# SwitchPower.net
KiCad netlist of a schematic drawn in Altium Designer
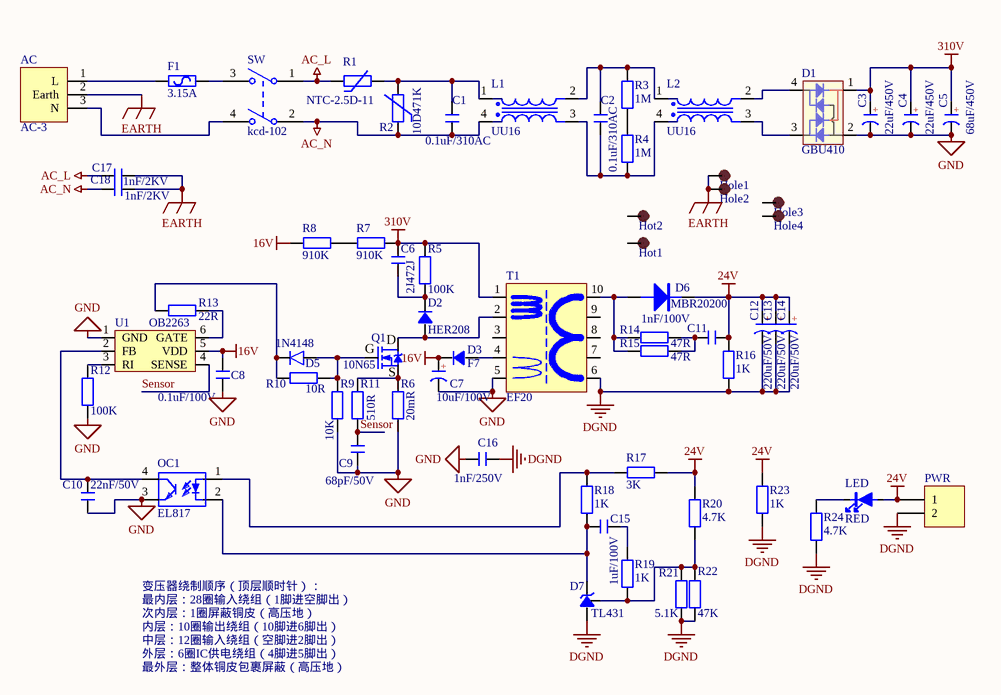
[diagram p0: SwitchPower.SchDoc]

(export (version "E")
  (design (tool "Eeschema 10.0.6"))
  (components
    (comp (ref "AC")
      (value "AC-3")
      (footprint "AC-3_1")
      (description "交流市电接口3芯")
      (libsource (lib "LovelessingSch") (part "AC-3"))
    )
    (comp (ref "C1")
      (value "0.1uF/310AC")
      (footprint "CX 10*13*11")
      (description "无极性贴片电容")
      (libsource (lib "LovelessingSch") (part "C"))
    )
    (comp (ref "C2")
      (value "0.1uF/310AC")
      (footprint "CX 10*13*11")
      (description "无极性贴片电容")
      (libsource (lib "LovelessingSch") (part "C"))
    )
    (comp (ref "C3")
      (value "22uF/450V")
      (footprint "CAP 5.0*12.5*20 - GD")
      (description "贴片电解电容")
      (libsource (lib "LovelessingSch") (part "C-CM"))
    )
    (comp (ref "C4")
      (value "22uF/450V")
      (footprint "CAP 5.0*12.5*20 - GD")
      (description "贴片电解电容")
      (libsource (lib "LovelessingSch") (part "C-CM"))
    )
    (comp (ref "C5")
      (value "68uF/450V")
      (footprint "CAP 7.5*18*35.5-H - GD")
      (description "贴片电解电容")
      (libsource (lib "LovelessingSch") (part "C-CM"))
    )
    (comp (ref "C6")
      (value "2J472J")
      (footprint "CBB 5*6.3*3")
      (description "无极性贴片电容")
      (libsource (lib "LovelessingSch") (part "C"))
    )
    (comp (ref "C7")
      (value "10uF/100V")
      (footprint "CAP 2.5*5*11 - GD")
      (description "贴片电解电容")
      (libsource (lib "LovelessingSch") (part "C-CM"))
    )
    (comp (ref "C8")
      (value "0.1uF/100V")
      (footprint "C 0805_L")
      (description "无极性贴片电容")
      (libsource (lib "LovelessingSch") (part "C"))
    )
    (comp (ref "C9")
      (value "68pF/50V")
      (footprint "C 0805_L")
      (description "无极性贴片电容")
      (libsource (lib "LovelessingSch") (part "C"))
    )
    (comp (ref "C10")
      (value "22nF/50V")
      (footprint "C 0805_L")
      (description "无极性贴片电容")
      (libsource (lib "LovelessingSch") (part "C"))
    )
    (comp (ref "C11")
      (value "1nF/100V")
      (footprint "C 1206_L")
      (description "无极性贴片电容")
      (libsource (lib "LovelessingSch") (part "C"))
    )
    (comp (ref "C12")
      (value "220uF/50V")
      (footprint "CAP 5.0*10*20 - GD")
      (description "贴片电解电容")
      (libsource (lib "LovelessingSch") (part "C-CM"))
    )
    (comp (ref "C13")
      (value "220uF/50V")
      (footprint "CAP 5.0*10*20 - GD")
      (description "贴片电解电容")
      (libsource (lib "LovelessingSch") (part "C-CM"))
    )
    (comp (ref "C14")
      (value "220uF/50V")
      (footprint "CAP 5.0*10*20 - GD")
      (description "贴片电解电容")
      (libsource (lib "LovelessingSch") (part "C-CM"))
    )
    (comp (ref "C15")
      (value "1uF/100V")
      (footprint "C 1206_L")
      (description "无极性贴片电容")
      (libsource (lib "LovelessingSch") (part "C"))
    )
    (comp (ref "C16")
      (value "1nF/250V")
      (footprint "CY 10*14*5")
      (description "无极性贴片电容")
      (libsource (lib "LovelessingSch") (part "C"))
    )
    (comp (ref "C17")
      (value "1nF/2KV")
      (footprint "CY 10*14*5")
      (description "无极性贴片电容")
      (libsource (lib "LovelessingSch") (part "C"))
    )
    (comp (ref "C18")
      (value "1nF/2KV")
      (footprint "CY 10*14*5")
      (description "无极性贴片电容")
      (libsource (lib "LovelessingSch") (part "C"))
    )
    (comp (ref "D1")
      (value "GBU410")
      (footprint "GBU")
      (description "整流桥")
      (libsource (lib "LovelessingSch") (part "RectifierBridge"))
    )
    (comp (ref "D2")
      (value "HER208")
      (footprint "DO-15V")
      (description "开关二级管")
      (libsource (lib "LovelessingSch") (part "D-US1M"))
    )
    (comp (ref "D3")
      (value "F7")
      (footprint "SOD-123F")
      (description "开关二级管")
      (libsource (lib "LovelessingSch") (part "D-US1M"))
    )
    (comp (ref "D5")
      (value "1N4148")
      (footprint "SOD-123F")
      (description "二极管")
      (libsource (lib "LovelessingSch") (part "D"))
    )
    (comp (ref "D6")
      (value "MBR20200")
      (footprint "TO220A")
      (description "整流二极管")
      (libsource (lib "LovelessingSch") (part "DIODE"))
    )
    (comp (ref "D7")
      (value "TL431")
      (footprint "SOT23-3L")
      (description "稳压二极管")
      (libsource (lib "LovelessingSch") (part "TL431"))
    )
    (comp (ref "F1")
      (value "3.15A")
      (footprint "FU 4x16_V")
      (description "保险丝")
      (libsource (lib "LovelessingSch") (part "FUSE"))
    )
    (comp (ref "Hole1")
      (value "hole")
      (footprint "M3")
      (description "测试点")
      (libsource (lib "LovelessingSch") (part "TEST-POINT"))
    )
    (comp (ref "Hole2")
      (value "hole")
      (footprint "M3")
      (description "测试点")
      (libsource (lib "LovelessingSch") (part "TEST-POINT"))
    )
    (comp (ref "Hole3")
      (value "hole")
      (footprint "M3")
      (description "测试点")
      (libsource (lib "LovelessingSch") (part "TEST-POINT"))
    )
    (comp (ref "Hole4")
      (value "hole")
      (footprint "M3")
      (description "测试点")
      (libsource (lib "LovelessingSch") (part "TEST-POINT"))
    )
    (comp (ref "Hot1")
      (value "TEST POINT")
      (footprint "SRP16-24-25")
      (description "测试点")
      (libsource (lib "LovelessingSch") (part "TEST-POINT"))
    )
    (comp (ref "Hot2")
      (value "TEST POINT")
      (footprint "SRP16-24-25")
      (description "测试点")
      (libsource (lib "LovelessingSch") (part "TEST-POINT"))
    )
    (comp (ref "L1")
      (value "UU16")
      (footprint "UU10.5")
      (description "共模电感")
      (libsource (lib "LovelessingSch") (part "DLW21SN900SQ2L"))
    )
    (comp (ref "L2")
      (value "UU16")
      (footprint "UU10.5")
      (description "共模电感")
      (libsource (lib "LovelessingSch") (part "DLW21SN900SQ2L"))
    )
    (comp (ref "LED")
      (value "RED")
      (footprint "LED 0805R")
      (description "发光二极管")
      (libsource (lib "LovelessingSch") (part "LED"))
    )
    (comp (ref "OC1")
      (value "EL817")
      (footprint "DIP4-300")
      (description "线性光耦")
      (libsource (lib "LovelessingSch") (part "EL817"))
    )
    (comp (ref "PWR")
      (value "~")
      (footprint "VH3.96-LI-2P")
      (description "Header, 2-Pin")
      (fields (field (name "PUBLISHER") "Altium Limited"))
      (libsource (lib "LovelessingSch") (part "Header 2"))
    )
    (comp (ref "Q1")
      (value "10N65")
      (footprint "TO220A")
      (description "NMOS 75V+80A 7.4mΩ")
      (libsource (lib "LovelessingSch") (part "IRFS3607PBF"))
    )
    (comp (ref "R1")
      (value "NTC-2.5D-11")
      (footprint "VDR NTC2.5D-11")
      (description "热敏电阻")
      (libsource (lib "LovelessingSch") (part "R_NTC"))
    )
    (comp (ref "R2")
      (value "10D471K")
      (footprint "R VDR-12.5*16.5-T")
      (description "压敏电阻")
      (libsource (lib "LovelessingSch") (part "R_VDR"))
    )
    (comp (ref "R3")
      (value "1M")
      (footprint "R 1206_L")
      (description "贴片电阻")
      (libsource (lib "LovelessingSch") (part "R"))
    )
    (comp (ref "R4")
      (value "1M")
      (footprint "R 1206_L")
      (description "贴片电阻")
      (libsource (lib "LovelessingSch") (part "R"))
    )
    (comp (ref "R5")
      (value "100K")
      (footprint "AXIAL0.8-2W-V")
      (description "贴片电阻")
      (libsource (lib "LovelessingSch") (part "R"))
    )
    (comp (ref "R6")
      (value "20mR")
      (footprint "AXIAL0.8-2W-V")
      (description "贴片电阻")
      (libsource (lib "LovelessingSch") (part "R"))
    )
    (comp (ref "R7")
      (value "910K")
      (footprint "R 1206_L")
      (description "贴片电阻")
      (libsource (lib "LovelessingSch") (part "R"))
    )
    (comp (ref "R8")
      (value "910K")
      (footprint "R 1206_L")
      (description "贴片电阻")
      (libsource (lib "LovelessingSch") (part "R"))
    )
    (comp (ref "R9")
      (value "10K")
      (footprint "R 1206_L")
      (description "贴片电阻")
      (libsource (lib "LovelessingSch") (part "R"))
    )
    (comp (ref "R10")
      (value "10R")
      (footprint "R 0805_L")
      (description "贴片电阻")
      (libsource (lib "LovelessingSch") (part "R"))
    )
    (comp (ref "R11")
      (value "510R")
      (footprint "R 1206_L")
      (description "贴片电阻")
      (libsource (lib "LovelessingSch") (part "R"))
    )
    (comp (ref "R12")
      (value "100K")
      (footprint "R 0805_L")
      (description "贴片电阻")
      (libsource (lib "LovelessingSch") (part "R"))
    )
    (comp (ref "R13")
      (value "22R")
      (footprint "R 1206_L")
      (description "贴片电阻")
      (libsource (lib "LovelessingSch") (part "R"))
    )
    (comp (ref "R14")
      (value "47R")
      (footprint "R 1206_L")
      (description "贴片电阻")
      (libsource (lib "LovelessingSch") (part "R"))
    )
    (comp (ref "R15")
      (value "47R")
      (footprint "R 1206_L")
      (description "贴片电阻")
      (libsource (lib "LovelessingSch") (part "R"))
    )
    (comp (ref "R16")
      (value "1K")
      (footprint "R 1206_L")
      (description "贴片电阻")
      (libsource (lib "LovelessingSch") (part "R"))
    )
    (comp (ref "R17")
      (value "3K")
      (footprint "R 0805_L")
      (description "贴片电阻")
      (libsource (lib "LovelessingSch") (part "R"))
    )
    (comp (ref "R18")
      (value "1K")
      (footprint "R 0805_L")
      (description "贴片电阻")
      (libsource (lib "LovelessingSch") (part "R"))
    )
    (comp (ref "R19")
      (value "1K")
      (footprint "R 0805_L")
      (description "贴片电阻")
      (libsource (lib "LovelessingSch") (part "R"))
    )
    (comp (ref "R20")
      (value "4.7K")
      (footprint "R 0805_L")
      (description "贴片电阻")
      (libsource (lib "LovelessingSch") (part "R"))
    )
    (comp (ref "R21")
      (value "5.1K")
      (footprint "R 0805_L")
      (description "贴片电阻")
      (libsource (lib "LovelessingSch") (part "R"))
    )
    (comp (ref "R22")
      (value "47K")
      (footprint "R 0805_L")
      (description "贴片电阻")
      (libsource (lib "LovelessingSch") (part "R"))
    )
    (comp (ref "R23")
      (value "1K")
      (footprint "R 1206_L")
      (description "贴片电阻")
      (libsource (lib "LovelessingSch") (part "R"))
    )
    (comp (ref "R24")
      (value "4.7K")
      (footprint "R 1206_L")
      (description "贴片电阻")
      (libsource (lib "LovelessingSch") (part "R"))
    )
    (comp (ref "SW")
      (value "kcd-102")
      (footprint "KCD1-104-W")
      (description "双刀单掷开关")
      (libsource (lib "LovelessingSch") (part "Switch_2"))
    )
    (comp (ref "T1")
      (value "EF20")
      (footprint "EI28X30")
      (description "开关电源变压器")
      (libsource (lib "LovelessingSch") (part "EF20"))
    )
    (comp (ref "U1")
      (value "OB2263")
      (footprint "SOT23-6L")
      (description "开关电源IC")
      (libsource (lib "LovelessingSch") (part "OB2263"))
    )
  )
  (nets
    (net (code "1") (name "/Sensor") (class "Default")
      (node (ref "C9") (pin "1") (pinfunction "1_1") (pintype "passive"))
      (node (ref "R11") (pin "1") (pinfunction "1_1") (pintype "passive"))
      (node (ref "U1") (pin "4") (pinfunction "SENSE_4") (pintype "passive"))
    )
    (net (code "2") (name "16V") (class "Default")
      (node (ref "C7") (pin "1") (pinfunction "A_1") (pintype "passive"))
      (node (ref "C8") (pin "1") (pinfunction "1_1") (pintype "passive"))
      (node (ref "D3") (pin "2") (pinfunction "2_2") (pintype "passive"))
      (node (ref "R8") (pin "1") (pinfunction "1_1") (pintype "passive"))
      (node (ref "U1") (pin "5") (pinfunction "VDD_5") (pintype "passive"))
    )
    (net (code "3") (name "24V") (class "Default")
      (node (ref "C11") (pin "1") (pinfunction "1_1") (pintype "passive"))
      (node (ref "C12") (pin "1") (pinfunction "A_1") (pintype "passive"))
      (node (ref "C13") (pin "1") (pinfunction "A_1") (pintype "passive"))
      (node (ref "C14") (pin "1") (pinfunction "A_1") (pintype "passive"))
      (node (ref "D6") (pin "2") (pinfunction "K_2") (pintype "passive"))
      (node (ref "LED") (pin "1") (pinfunction "1_1") (pintype "passive"))
      (node (ref "PWR") (pin "1") (pinfunction "1_1") (pintype "passive"))
      (node (ref "R16") (pin "1") (pinfunction "1_1") (pintype "passive"))
      (node (ref "R17") (pin "1") (pinfunction "1_1") (pintype "passive"))
      (node (ref "R20") (pin "2") (pinfunction "2_2") (pintype "passive"))
      (node (ref "R23") (pin "1") (pinfunction "1_1") (pintype "passive"))
    )
    (net (code "4") (name "310V") (class "Default")
      (node (ref "C3") (pin "1") (pinfunction "A_1") (pintype "passive"))
      (node (ref "C4") (pin "1") (pinfunction "A_1") (pintype "passive"))
      (node (ref "C5") (pin "1") (pinfunction "A_1") (pintype "passive"))
      (node (ref "C6") (pin "2") (pinfunction "2_2") (pintype "passive"))
      (node (ref "D1") (pin "1") (pinfunction "+_1") (pintype "passive"))
      (node (ref "R5") (pin "2") (pinfunction "2_2") (pintype "passive"))
      (node (ref "R7") (pin "2") (pinfunction "2_2") (pintype "passive"))
      (node (ref "T1") (pin "1") (pinfunction "GND_1") (pintype "passive"))
    )
    (net (code "5") (name "AC_L") (class "Default")
      (node (ref "C17") (pin "2") (pinfunction "2_2") (pintype "passive"))
      (node (ref "R1") (pin "1") (pinfunction "1_1") (pintype "passive"))
      (node (ref "SW") (pin "1") (pinfunction "1_1") (pintype "passive"))
    )
    (net (code "6") (name "AC_N") (class "Default")
      (node (ref "C1") (pin "1") (pinfunction "1_1") (pintype "passive"))
      (node (ref "C18") (pin "2") (pinfunction "2_2") (pintype "passive"))
      (node (ref "L1") (pin "4") (pintype "passive"))
      (node (ref "R2") (pin "1") (pinfunction "1_1") (pintype "passive"))
      (node (ref "SW") (pin "2") (pinfunction "2_2") (pintype "passive"))
    )
    (net (code "7") (name "DGND") (class "Default")
      (node (ref "C12") (pin "2") (pinfunction "K_2") (pintype "passive"))
      (node (ref "C13") (pin "2") (pinfunction "K_2") (pintype "passive"))
      (node (ref "C14") (pin "2") (pinfunction "K_2") (pintype "passive"))
      (node (ref "C16") (pin "1") (pinfunction "1_1") (pintype "passive"))
      (node (ref "D7") (pin "3") (pintype "passive"))
      (node (ref "PWR") (pin "2") (pinfunction "2_2") (pintype "passive"))
      (node (ref "R16") (pin "2") (pinfunction "2_2") (pintype "passive"))
      (node (ref "R21") (pin "1") (pinfunction "1_1") (pintype "passive"))
      (node (ref "R22") (pin "1") (pinfunction "1_1") (pintype "passive"))
      (node (ref "R23") (pin "2") (pinfunction "2_2") (pintype "passive"))
      (node (ref "R24") (pin "2") (pinfunction "2_2") (pintype "passive"))
      (node (ref "T1") (pin "6") (pinfunction "DRAIN_6") (pintype "passive"))
    )
    (net (code "8") (name "EARTH") (class "Default")
      (node (ref "AC") (pin "2") (pinfunction "Earth_2") (pintype "passive"))
      (node (ref "C17") (pin "1") (pinfunction "1_1") (pintype "passive"))
      (node (ref "C18") (pin "1") (pinfunction "1_1") (pintype "passive"))
      (node (ref "Hole1") (pin "1") (pinfunction "1_1") (pintype "passive"))
      (node (ref "Hole2") (pin "1") (pinfunction "1_1") (pintype "passive"))
    )
    (net (code "9") (name "GND") (class "Default")
      (node (ref "C10") (pin "2") (pinfunction "2_2") (pintype "passive"))
      (node (ref "C16") (pin "2") (pinfunction "2_2") (pintype "passive"))
      (node (ref "C3") (pin "2") (pinfunction "K_2") (pintype "passive"))
      (node (ref "C4") (pin "2") (pinfunction "K_2") (pintype "passive"))
      (node (ref "C5") (pin "2") (pinfunction "K_2") (pintype "passive"))
      (node (ref "C7") (pin "2") (pinfunction "K_2") (pintype "passive"))
      (node (ref "C8") (pin "2") (pinfunction "2_2") (pintype "passive"))
      (node (ref "C9") (pin "2") (pinfunction "2_2") (pintype "passive"))
      (node (ref "D1") (pin "2") (pinfunction "-_2") (pintype "passive"))
      (node (ref "OC1") (pin "3") (pinfunction "E_3") (pintype "passive"))
      (node (ref "R12") (pin "1") (pinfunction "1_1") (pintype "passive"))
      (node (ref "R6") (pin "1") (pinfunction "1_1") (pintype "passive"))
      (node (ref "R9") (pin "1") (pinfunction "1_1") (pintype "passive"))
      (node (ref "T1") (pin "5") (pinfunction "DRAIN_5") (pintype "passive"))
      (node (ref "U1") (pin "1") (pinfunction "GND_1") (pintype "passive"))
    )
    (net (code "10") (name "Net-(AC-L)") (class "Default")
      (node (ref "AC") (pin "1") (pinfunction "L_1") (pintype "passive"))
      (node (ref "F1") (pin "1") (pinfunction "1_1") (pintype "passive"))
    )
    (net (code "11") (name "Net-(AC-N)") (class "Default")
      (node (ref "AC") (pin "3") (pinfunction "N_3") (pintype "passive"))
      (node (ref "SW") (pin "4") (pinfunction "4_4") (pintype "passive"))
    )
    (net (code "12") (name "Net-(C1-Pad2)") (class "Default")
      (node (ref "C1") (pin "2") (pinfunction "2_2") (pintype "passive"))
      (node (ref "L1") (pin "1") (pintype "passive"))
      (node (ref "R1") (pin "2") (pinfunction "2_2") (pintype "passive"))
      (node (ref "R2") (pin "2") (pinfunction "2_2") (pintype "passive"))
    )
    (net (code "13") (name "Net-(C2-Pad1)") (class "Default")
      (node (ref "C2") (pin "1") (pinfunction "1_1") (pintype "passive"))
      (node (ref "L1") (pin "3") (pintype "passive"))
      (node (ref "L2") (pin "4") (pintype "passive"))
      (node (ref "R4") (pin "1") (pinfunction "1_1") (pintype "passive"))
    )
    (net (code "14") (name "Net-(C2-Pad2)") (class "Default")
      (node (ref "C2") (pin "2") (pinfunction "2_2") (pintype "passive"))
      (node (ref "L1") (pin "2") (pintype "passive"))
      (node (ref "L2") (pin "1") (pintype "passive"))
      (node (ref "R3") (pin "2") (pinfunction "2_2") (pintype "passive"))
    )
    (net (code "15") (name "Net-(C6-Pad1)") (class "Default")
      (node (ref "C6") (pin "1") (pinfunction "1_1") (pintype "passive"))
      (node (ref "D2") (pin "2") (pinfunction "2_2") (pintype "passive"))
      (node (ref "R5") (pin "1") (pinfunction "1_1") (pintype "passive"))
    )
    (net (code "16") (name "Net-(C11-Pad2)") (class "Default")
      (node (ref "C11") (pin "2") (pinfunction "2_2") (pintype "passive"))
      (node (ref "R14") (pin "1") (pinfunction "1_1") (pintype "passive"))
      (node (ref "R15") (pin "1") (pinfunction "1_1") (pintype "passive"))
    )
    (net (code "17") (name "Net-(C15-Pad1)") (class "Default")
      (node (ref "C15") (pin "1") (pinfunction "1_1") (pintype "passive"))
      (node (ref "R19") (pin "1") (pinfunction "1_1") (pintype "passive"))
    )
    (net (code "18") (name "Net-(D1-AC-Pad3)") (class "Default")
      (node (ref "D1") (pin "3") (pinfunction "AC_3") (pintype "passive"))
      (node (ref "L2") (pin "3") (pintype "passive"))
    )
    (net (code "19") (name "Net-(D1-AC-Pad4)") (class "Default")
      (node (ref "D1") (pin "4") (pinfunction "AC_4") (pintype "passive"))
      (node (ref "L2") (pin "2") (pintype "passive"))
    )
    (net (code "20") (name "Net-(D5-Pad2)") (class "Default")
      (node (ref "D5") (pin "2") (pintype "passive"))
      (node (ref "R10") (pin "2") (pinfunction "2_2") (pintype "passive"))
      (node (ref "R13") (pin "2") (pinfunction "2_2") (pintype "passive"))
    )
    (net (code "21") (name "Net-(D6-A)") (class "Default")
      (node (ref "D6") (pin "1") (pinfunction "A_1") (pintype "passive"))
      (node (ref "R14") (pin "2") (pinfunction "2_2") (pintype "passive"))
      (node (ref "R15") (pin "2") (pinfunction "2_2") (pintype "passive"))
      (node (ref "T1") (pin "10") (pinfunction "DRAIN_10") (pintype "passive"))
    )
    (net (code "22") (name "Net-(D7-Pad1)") (class "Default")
      (node (ref "D7") (pin "1") (pintype "passive"))
      (node (ref "R19") (pin "2") (pinfunction "2_2") (pintype "passive"))
      (node (ref "R20") (pin "1") (pinfunction "1_1") (pintype "passive"))
      (node (ref "R21") (pin "2") (pinfunction "2_2") (pintype "passive"))
      (node (ref "R22") (pin "2") (pinfunction "2_2") (pintype "passive"))
    )
    (net (code "23") (name "Net-(F1-Pad2)") (class "Default")
      (node (ref "F1") (pin "2") (pinfunction "2_2") (pintype "passive"))
      (node (ref "SW") (pin "3") (pinfunction "3_3") (pintype "passive"))
    )
    (net (code "24") (name "Net-(LED-Pad2)") (class "Default")
      (node (ref "LED") (pin "2") (pinfunction "2_2") (pintype "passive"))
      (node (ref "R24") (pin "1") (pinfunction "1_1") (pintype "passive"))
    )
    (net (code "25") (name "Net-(OC1-A)") (class "Default")
      (node (ref "OC1") (pin "1") (pinfunction "A_1") (pintype "passive"))
      (node (ref "R17") (pin "2") (pinfunction "2_2") (pintype "passive"))
      (node (ref "R18") (pin "1") (pinfunction "1_1") (pintype "passive"))
    )
    (net (code "26") (name "Net-(OC1-C)") (class "Default")
      (node (ref "C10") (pin "1") (pinfunction "1_1") (pintype "passive"))
      (node (ref "OC1") (pin "4") (pinfunction "C_4") (pintype "passive"))
      (node (ref "U1") (pin "2") (pinfunction "FB_2") (pintype "passive"))
    )
    (net (code "27") (name "Net-(OC1-K)") (class "Default")
      (node (ref "C15") (pin "2") (pinfunction "2_2") (pintype "passive"))
      (node (ref "D7") (pin "2") (pintype "passive"))
      (node (ref "OC1") (pin "2") (pinfunction "K_2") (pintype "passive"))
      (node (ref "R18") (pin "2") (pinfunction "2_2") (pintype "passive"))
    )
    (net (code "28") (name "Net-(Q1-D)") (class "Default")
      (node (ref "D2") (pin "1") (pinfunction "1_1") (pintype "passive"))
      (node (ref "Q1") (pin "2") (pinfunction "D_2") (pintype "passive"))
      (node (ref "T1") (pin "2") (pinfunction "GND_2") (pintype "passive"))
    )
    (net (code "29") (name "Net-(Q1-G)") (class "Default")
      (node (ref "D5") (pin "1") (pintype "passive"))
      (node (ref "Q1") (pin "1") (pinfunction "G_1") (pintype "passive"))
      (node (ref "R10") (pin "1") (pinfunction "1_1") (pintype "passive"))
      (node (ref "R9") (pin "2") (pinfunction "2_2") (pintype "passive"))
    )
    (net (code "30") (name "Net-(Q1-S)") (class "Default")
      (node (ref "Q1") (pin "3") (pinfunction "S_3") (pintype "passive"))
      (node (ref "R11") (pin "2") (pinfunction "2_2") (pintype "passive"))
      (node (ref "R6") (pin "2") (pinfunction "2_2") (pintype "passive"))
    )
    (net (code "31") (name "Net-(R3-Pad1)") (class "Default")
      (node (ref "R3") (pin "1") (pinfunction "1_1") (pintype "passive"))
      (node (ref "R4") (pin "2") (pinfunction "2_2") (pintype "passive"))
    )
    (net (code "32") (name "Net-(R7-Pad1)") (class "Default")
      (node (ref "R7") (pin "1") (pinfunction "1_1") (pintype "passive"))
      (node (ref "R8") (pin "2") (pinfunction "2_2") (pintype "passive"))
    )
    (net (code "33") (name "Net-(T1-VCC)") (class "Default")
      (node (ref "D3") (pin "1") (pinfunction "1_1") (pintype "passive"))
      (node (ref "T1") (pin "4") (pinfunction "VCC_4") (pintype "passive"))
    )
    (net (code "34") (name "Net-(U1-GATE)") (class "Default")
      (node (ref "R13") (pin "1") (pinfunction "1_1") (pintype "passive"))
      (node (ref "U1") (pin "6") (pinfunction "GATE_6") (pintype "passive"))
    )
    (net (code "35") (name "Net-(U1-RI)") (class "Default")
      (node (ref "R12") (pin "2") (pinfunction "2_2") (pintype "passive"))
      (node (ref "U1") (pin "3") (pinfunction "RI_3") (pintype "passive"))
    )
    (net (code "36") (name "unconnected-(Hole3-Pad1)") (class "Default")
      (node (ref "Hole3") (pin "1") (pinfunction "1_1") (pintype "passive"))
    )
    (net (code "37") (name "unconnected-(Hole4-Pad1)") (class "Default")
      (node (ref "Hole4") (pin "1") (pinfunction "1_1") (pintype "passive"))
    )
    (net (code "38") (name "unconnected-(Hot1-Pad1)") (class "Default")
      (node (ref "Hot1") (pin "1") (pinfunction "1_1") (pintype "passive"))
    )
    (net (code "39") (name "unconnected-(Hot2-Pad1)") (class "Default")
      (node (ref "Hot2") (pin "1") (pinfunction "1_1") (pintype "passive"))
    )
    (net (code "40") (name "unconnected-(T1-NC-Pad3)") (class "Default")
      (node (ref "T1") (pin "3") (pinfunction "NC_3") (pintype "passive"))
    )
    (net (code "41") (name "unconnected-(T1-NC-Pad7)") (class "Default")
      (node (ref "T1") (pin "7") (pinfunction "NC_7") (pintype "passive"))
    )
    (net (code "42") (name "unconnected-(T1-NC-Pad8)") (class "Default")
      (node (ref "T1") (pin "8") (pinfunction "NC_8") (pintype "passive"))
    )
    (net (code "43") (name "unconnected-(T1-NC-Pad9)") (class "Default")
      (node (ref "T1") (pin "9") (pinfunction "NC_9") (pintype "passive"))
    )
  )
)
